# CRDC.net
KiCad netlist of a schematic drawn in EAGLE
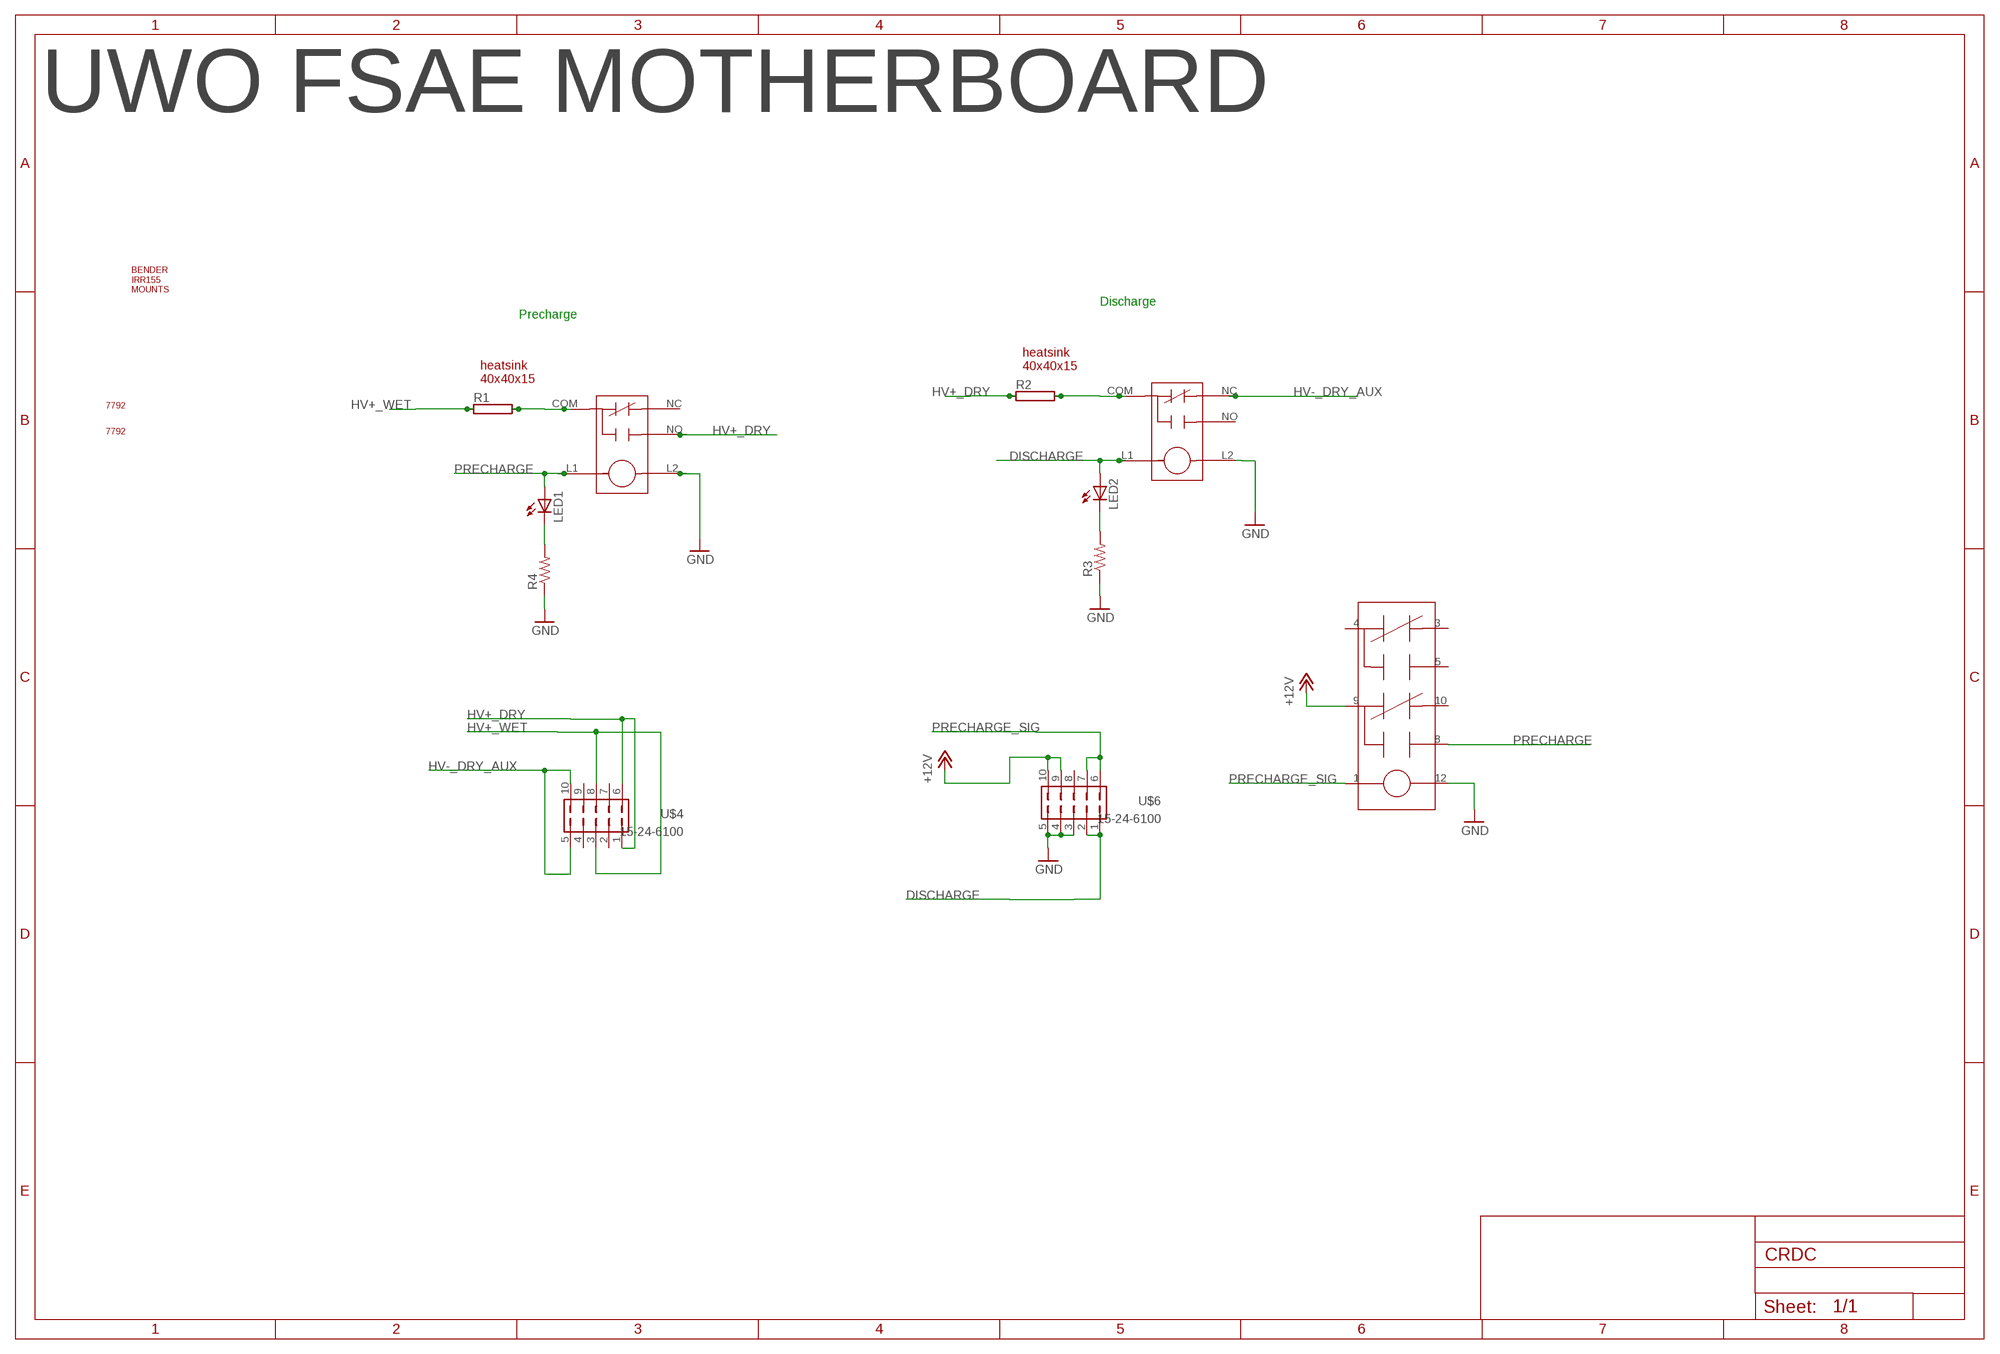
[diagram p0: schematic, sheet 1]

(export (version "E")
  (design (tool "Eeschema 10.0.6"))
  (components
    (comp (ref "LED1")
      (value "LED3MM")
      (footprint "eagle-import:LED3MM")
      (libsource (lib "eagle-import") (part "LED3MM"))
    )
    (comp (ref "LED2")
      (value "LED3MM")
      (footprint "eagle-import:LED3MM")
      (libsource (lib "eagle-import") (part "LED3MM"))
    )
    (comp (ref "R1")
      (value "RMG100-H")
      (footprint "eagle-import:TO-247-2H")
      (libsource (lib "eagle-import") (part "RMG100-H"))
    )
    (comp (ref "R2")
      (value "RMG100-H")
      (footprint "eagle-import:TO-247-2H")
      (libsource (lib "eagle-import") (part "RMG100-H"))
    )
    (comp (ref "R3")
      (value "R-US_R0805")
      (footprint "eagle-import:R0805")
      (libsource (lib "eagle-import") (part "R-US_R0805"))
    )
    (comp (ref "R4")
      (value "R-US_R0805")
      (footprint "eagle-import:R0805")
      (libsource (lib "eagle-import") (part "R-US_R0805"))
    )
    (comp (ref "U$1")
      (value "G81C335")
      (footprint "eagle-import:G81C335")
      (libsource (lib "eagle-import") (part "G81C335"))
    )
    (comp (ref "U$2")
      (value "G81C335")
      (footprint "eagle-import:G81C335")
      (libsource (lib "eagle-import") (part "G81C335"))
    )
    (comp (ref "U$3")
      (value "BENDER_IRR155")
      (footprint "eagle-import:BENDER_IRR155")
      (libsource (lib "eagle-import") (part "BENDER_IRR155"))
    )
    (comp (ref "U$4")
      (value "15-24-6100")
      (footprint "eagle-import:15-24-6100")
      (libsource (lib "eagle-import") (part "15-24-6100"))
    )
    (comp (ref "U$5")
      (value "7792")
      (footprint "eagle-import:7792")
      (libsource (lib "eagle-import") (part "7792"))
    )
    (comp (ref "U$6")
      (value "15-24-6100")
      (footprint "eagle-import:15-24-6100")
      (libsource (lib "eagle-import") (part "15-24-6100"))
    )
    (comp (ref "U$7")
      (value "V23079B1203B301")
      (footprint "eagle-import:V23079B1203B301")
      (libsource (lib "eagle-import") (part "V23079B1203B301"))
    )
    (comp (ref "U$8")
      (value "HEATSINK40X40X15")
      (footprint "eagle-import:HEATSINK40X40X15")
      (libsource (lib "eagle-import") (part "HEATSINK40X40X15"))
    )
    (comp (ref "U$9")
      (value "HEATSINK40X40X15")
      (footprint "eagle-import:HEATSINK40X40X15")
      (libsource (lib "eagle-import") (part "HEATSINK40X40X15"))
    )
    (comp (ref "U$10")
      (value "7792")
      (footprint "eagle-import:7792")
      (libsource (lib "eagle-import") (part "7792"))
    )
  )
  (nets
    (net (code "1") (name "+12V") (class "Default")
      (node (ref "U$6") (pin "10") (pinfunction "10_10") (pintype "passive"))
      (node (ref "U$6") (pin "9") (pinfunction "9_9") (pintype "passive"))
      (node (ref "U$7") (pin "9") (pinfunction "9_9") (pintype "bidirectional"))
    )
    (net (code "2") (name "/DISCHARGE") (class "Default")
      (node (ref "LED2") (pin "A") (pinfunction "A_A") (pintype "passive"))
      (node (ref "U$2") (pin "L1") (pinfunction "L1_L1") (pintype "bidirectional"))
      (node (ref "U$6") (pin "1") (pinfunction "1_1") (pintype "passive"))
      (node (ref "U$6") (pin "2") (pinfunction "2_2") (pintype "passive"))
    )
    (net (code "3") (name "/HV+_DRY") (class "Default")
      (node (ref "R2") (pin "1") (pinfunction "1_1") (pintype "passive"))
      (node (ref "U$1") (pin "NO") (pinfunction "NO_NO") (pintype "bidirectional"))
      (node (ref "U$4") (pin "1") (pinfunction "1_1") (pintype "passive"))
      (node (ref "U$4") (pin "6") (pinfunction "6_6") (pintype "passive"))
    )
    (net (code "4") (name "/HV+_WET") (class "Default")
      (node (ref "R1") (pin "1") (pinfunction "1_1") (pintype "passive"))
      (node (ref "U$4") (pin "3") (pinfunction "3_3") (pintype "passive"))
      (node (ref "U$4") (pin "8") (pinfunction "8_8") (pintype "passive"))
    )
    (net (code "5") (name "/HV-_DRY_AUX") (class "Default")
      (node (ref "U$2") (pin "NC") (pinfunction "NC_NC") (pintype "bidirectional"))
      (node (ref "U$4") (pin "10") (pinfunction "10_10") (pintype "passive"))
      (node (ref "U$4") (pin "5") (pinfunction "5_5") (pintype "passive"))
    )
    (net (code "6") (name "/PRECHARGE") (class "Default")
      (node (ref "LED1") (pin "A") (pinfunction "A_A") (pintype "passive"))
      (node (ref "U$1") (pin "L1") (pinfunction "L1_L1") (pintype "bidirectional"))
      (node (ref "U$7") (pin "8") (pinfunction "8_8") (pintype "bidirectional"))
    )
    (net (code "7") (name "/PRECHARGE_SIG") (class "Default")
      (node (ref "U$6") (pin "6") (pinfunction "6_6") (pintype "passive"))
      (node (ref "U$6") (pin "7") (pinfunction "7_7") (pintype "passive"))
      (node (ref "U$7") (pin "1") (pinfunction "1_1") (pintype "bidirectional"))
    )
    (net (code "8") (name "GND") (class "Default")
      (node (ref "R3") (pin "1") (pinfunction "1_1") (pintype "passive"))
      (node (ref "R4") (pin "1") (pinfunction "1_1") (pintype "passive"))
      (node (ref "U$1") (pin "L2") (pinfunction "L2_L2") (pintype "bidirectional"))
      (node (ref "U$2") (pin "L2") (pinfunction "L2_L2") (pintype "bidirectional"))
      (node (ref "U$6") (pin "3") (pinfunction "3_3") (pintype "passive"))
      (node (ref "U$6") (pin "4") (pinfunction "4_4") (pintype "passive"))
      (node (ref "U$6") (pin "5") (pinfunction "5_5") (pintype "passive"))
      (node (ref "U$7") (pin "12") (pinfunction "12_12") (pintype "bidirectional"))
    )
    (net (code "9") (name "Net-(LED1-C)") (class "Default")
      (node (ref "LED1") (pin "K") (pinfunction "C_K") (pintype "passive"))
      (node (ref "R4") (pin "2") (pinfunction "2_2") (pintype "passive"))
    )
    (net (code "10") (name "Net-(LED2-C)") (class "Default")
      (node (ref "LED2") (pin "K") (pinfunction "C_K") (pintype "passive"))
      (node (ref "R3") (pin "2") (pinfunction "2_2") (pintype "passive"))
    )
    (net (code "11") (name "Net-(R1-Pad2)") (class "Default")
      (node (ref "R1") (pin "2") (pinfunction "2_2") (pintype "passive"))
      (node (ref "U$1") (pin "COM") (pinfunction "COM_COM") (pintype "bidirectional"))
    )
    (net (code "12") (name "Net-(R2-Pad2)") (class "Default")
      (node (ref "R2") (pin "2") (pinfunction "2_2") (pintype "passive"))
      (node (ref "U$2") (pin "COM") (pinfunction "COM_COM") (pintype "bidirectional"))
    )
    (net (code "13") (name "unconnected-(U$1-PadNC)") (class "Default")
      (node (ref "U$1") (pin "NC") (pinfunction "NC_NC") (pintype "bidirectional"))
    )
    (net (code "14") (name "unconnected-(U$2-PadNO)") (class "Default")
      (node (ref "U$2") (pin "NO") (pinfunction "NO_NO") (pintype "bidirectional"))
    )
    (net (code "15") (name "unconnected-(U$4-Pad2)") (class "Default")
      (node (ref "U$4") (pin "2") (pinfunction "2_2") (pintype "passive"))
    )
    (net (code "16") (name "unconnected-(U$4-Pad4)") (class "Default")
      (node (ref "U$4") (pin "4") (pinfunction "4_4") (pintype "passive"))
    )
    (net (code "17") (name "unconnected-(U$4-Pad7)") (class "Default")
      (node (ref "U$4") (pin "7") (pinfunction "7_7") (pintype "passive"))
    )
    (net (code "18") (name "unconnected-(U$4-Pad9)") (class "Default")
      (node (ref "U$4") (pin "9") (pinfunction "9_9") (pintype "passive"))
    )
    (net (code "19") (name "unconnected-(U$6-Pad8)") (class "Default")
      (node (ref "U$6") (pin "8") (pinfunction "8_8") (pintype "passive"))
    )
    (net (code "20") (name "unconnected-(U$7-Pad3)") (class "Default")
      (node (ref "U$7") (pin "3") (pinfunction "3_3") (pintype "bidirectional"))
    )
    (net (code "21") (name "unconnected-(U$7-Pad4)") (class "Default")
      (node (ref "U$7") (pin "4") (pinfunction "4_4") (pintype "bidirectional"))
    )
    (net (code "22") (name "unconnected-(U$7-Pad5)") (class "Default")
      (node (ref "U$7") (pin "5") (pinfunction "5_5") (pintype "bidirectional"))
    )
    (net (code "23") (name "unconnected-(U$7-Pad10)") (class "Default")
      (node (ref "U$7") (pin "10") (pinfunction "10_10") (pintype "bidirectional"))
    )
  )
)
